# 1-Schematic_EMWAVER_V2_433_RAINSUN.net
KiCad netlist of a schematic drawn in EasyEDA
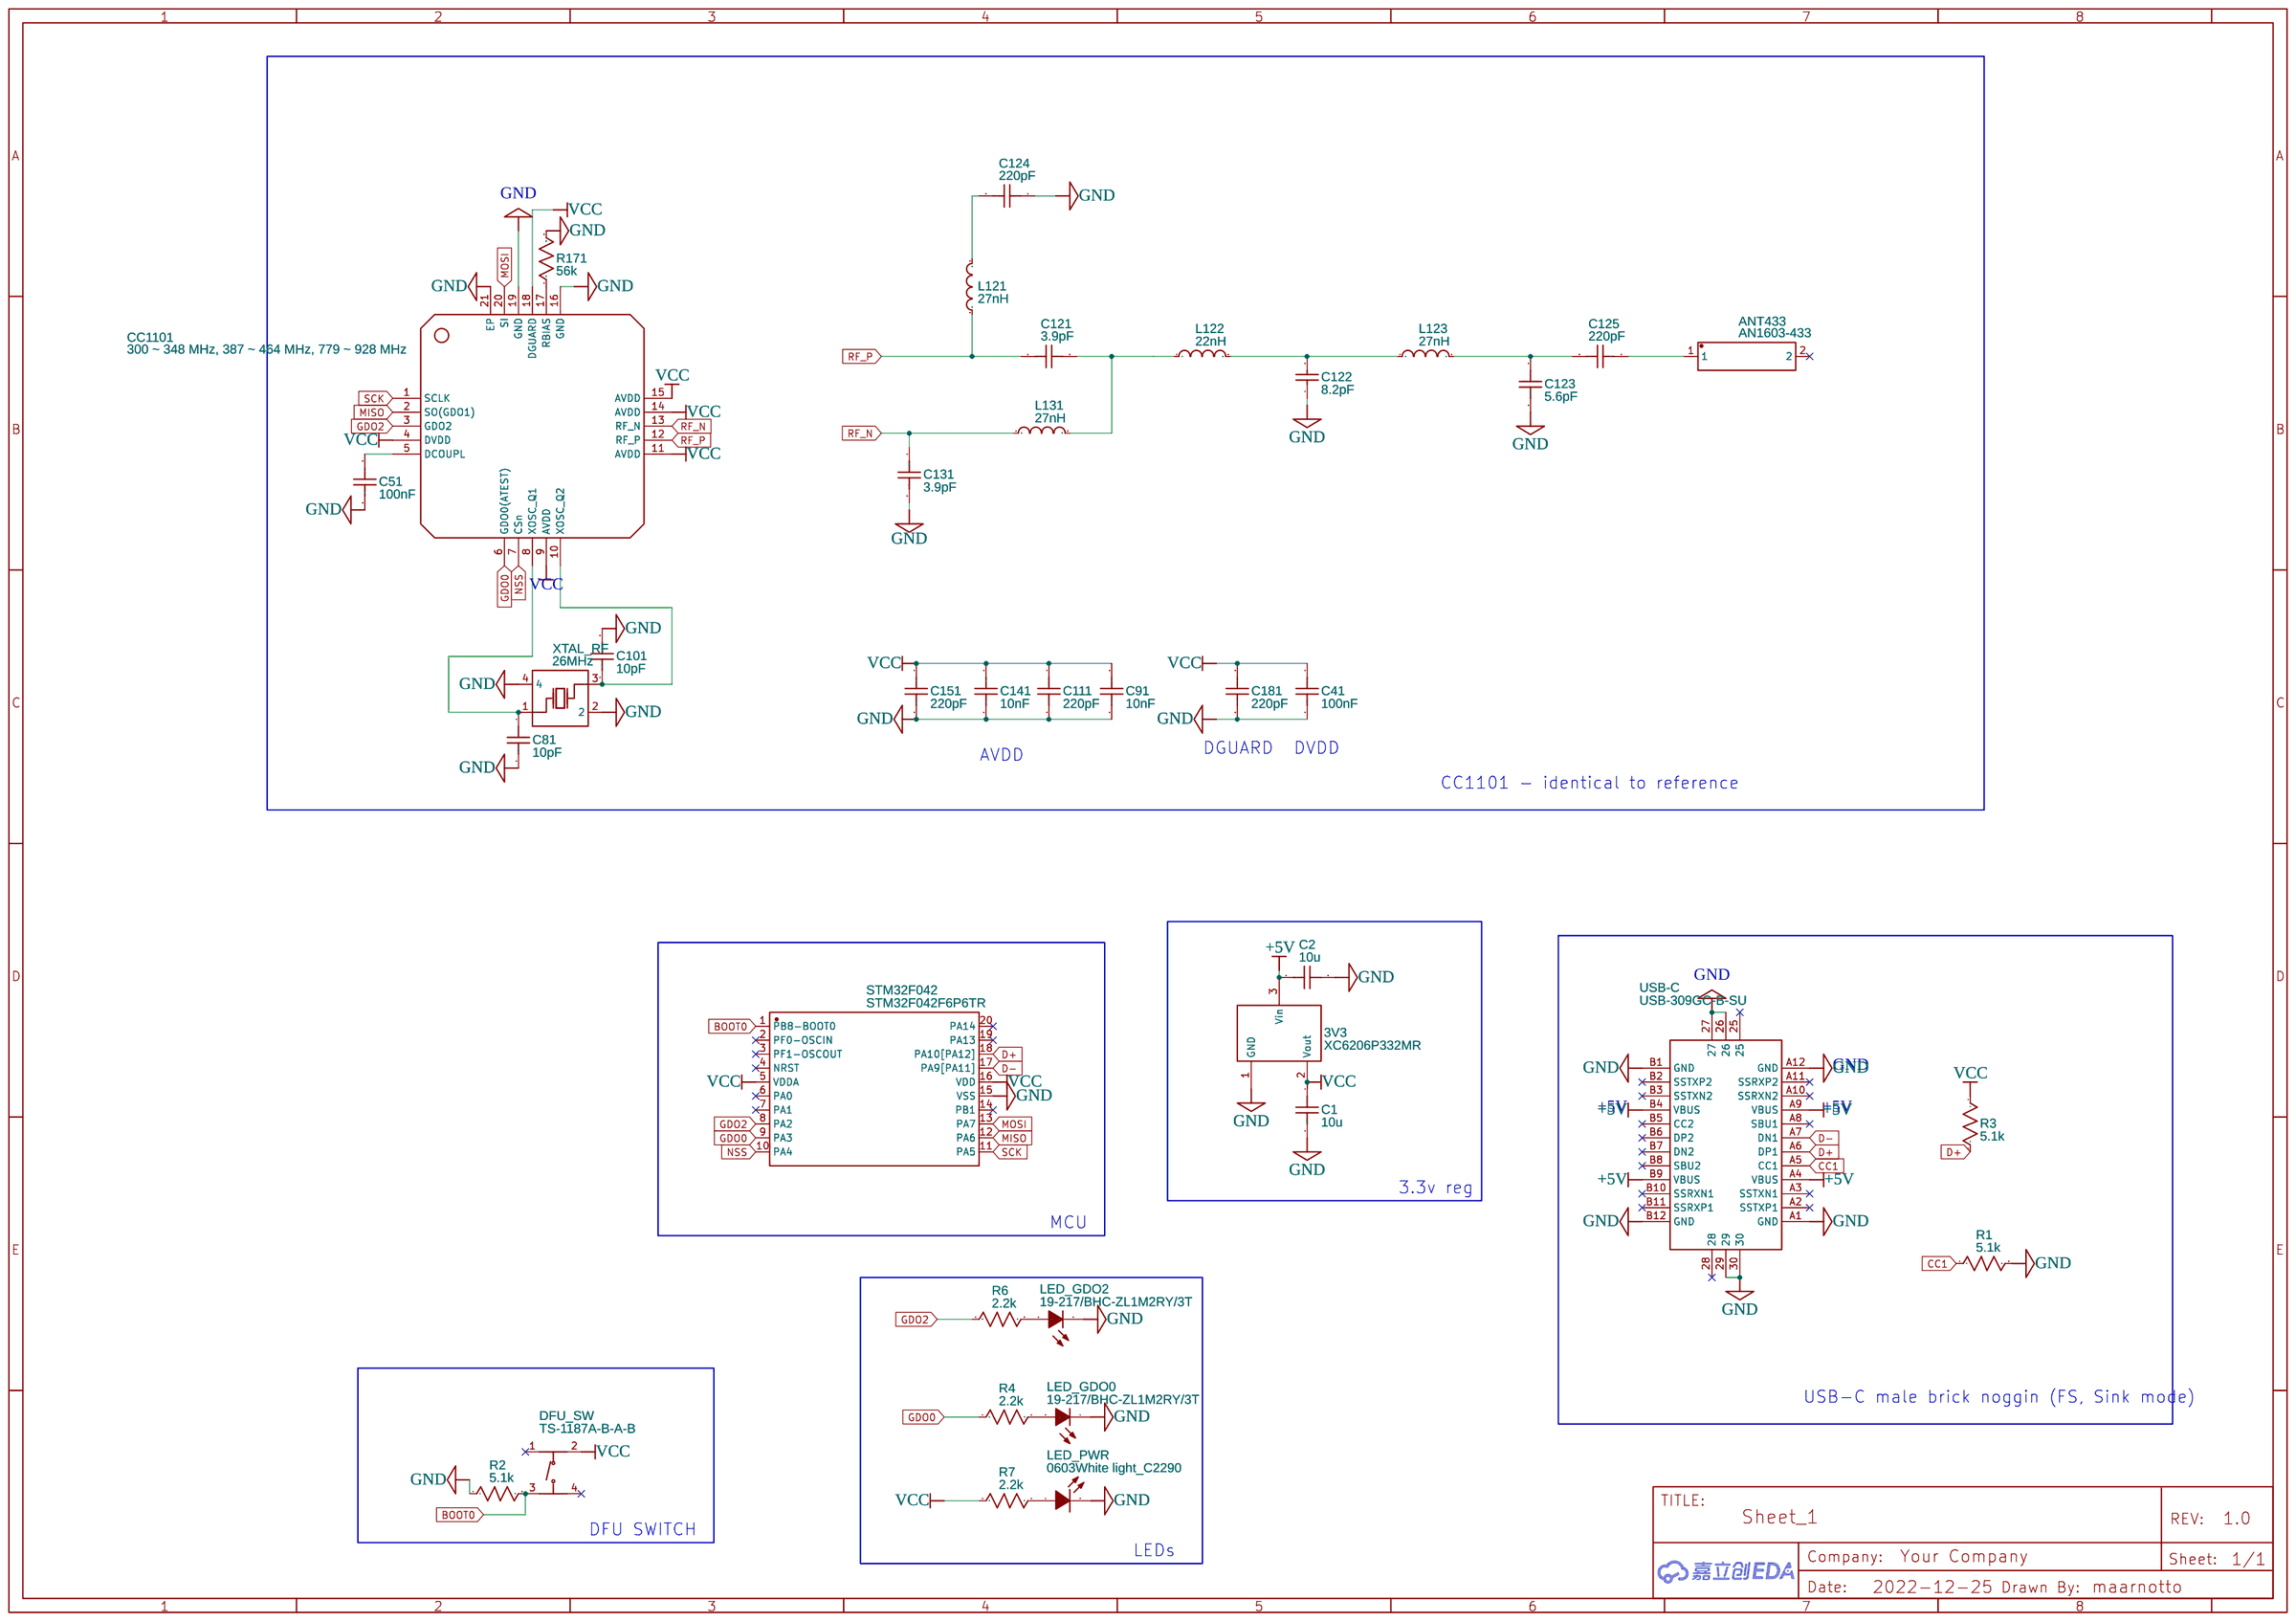
[diagram p0: schematic sheet]

(export (version "E")
  (design (tool "Eeschema 10.0.6"))
  (components
    (comp (ref "3V3")
      (value "XC6206P332MR")
      (fields (field (name "Manufacturer") "TOREX(特瑞仕)"))
      (libsource (lib "") (part "XC6206P332MR"))
    )
    (comp (ref "ANT433")
      (value "AN1603-433")
      (fields (field (name "Manufacturer") "rainsun(霖昱微)"))
      (libsource (lib "") (part "AN1603-433"))
    )
    (comp (ref "C1") (value "10u") (libsource (lib "") (part "C_0603_US")))
    (comp (ref "C2") (value "10u") (libsource (lib "") (part "C_0603_US_1")))
    (comp (ref "C41") (value "100nF") (libsource (lib "") (part "C_0402_US_1")))
    (comp (ref "C51") (value "100nF") (libsource (lib "") (part "C_0402_US_1")))
    (comp (ref "C81") (value "10pF") (libsource (lib "") (part "C_0402_US_1")))
    (comp (ref "C91") (value "10nF") (libsource (lib "") (part "C_0402_US_1")))
    (comp (ref "C101") (value "10pF") (libsource (lib "") (part "C_0402_US_2")))
    (comp (ref "C111") (value "220pF") (libsource (lib "") (part "C_0402_US_1")))
    (comp (ref "C121") (value "3.9pF") (libsource (lib "") (part "C_0402_US")))
    (comp (ref "C122")
      (value "8.2pF")
      (fields (field (name "Manufacturer Part") "0402CG8R2C500NT") (field (name "Manufacturer") "FH(风华)"))
      (libsource (lib "") (part "0402CG8R2C500NT"))
    )
    (comp (ref "C123") (value "5.6pF") (libsource (lib "") (part "C_0402_US_1")))
    (comp (ref "C124") (value "220pF") (libsource (lib "") (part "C_0402_US")))
    (comp (ref "C125") (value "220pF") (libsource (lib "") (part "C_0402_US")))
    (comp (ref "C131") (value "3.9pF") (libsource (lib "") (part "C_0402_US_1")))
    (comp (ref "C141") (value "10nF") (libsource (lib "") (part "C_0402_US_1")))
    (comp (ref "C151") (value "220pF") (libsource (lib "") (part "C_0402_US_1")))
    (comp (ref "C181") (value "220pF") (libsource (lib "") (part "C_0402_US_1")))
    (comp (ref "CC1101")
      (value "300 ~ 348 MHz, 387 ~ 464 MHz, 779 ~ 928 MHz")
      (fields (field (name "Manufacturer Part") "CC1101RGPR") (field (name "Manufacturer") "TI(德州仪器)"))
      (libsource (lib "") (part "CC1101RGPR"))
    )
    (comp (ref "DFU_SW")
      (value "TS-1187A-B-A-B")
      (fields (field (name "Manufacturer") "XKB Connectivity(中国星坤)"))
      (libsource (lib "") (part "TS-1187A-B-A-B"))
    )
    (comp (ref "L121") (value "27nH") (libsource (lib "") (part "L0402_US_1")))
    (comp (ref "L122") (value "22nH") (libsource (lib "") (part "L0402_US")))
    (comp (ref "L123") (value "27nH") (libsource (lib "") (part "L0402_US")))
    (comp (ref "L131") (value "27nH") (libsource (lib "") (part "L0402_US")))
    (comp (ref "LED_GDO0")
      (value "19-217/BHC-ZL1M2RY/3T")
      (fields (field (name "Manufacturer") "EVERLIGHT(亿光)"))
      (libsource (lib "") (part "19-217/BHC-ZL1M2RY/3T"))
    )
    (comp (ref "LED_GDO2")
      (value "19-217/BHC-ZL1M2RY/3T")
      (fields (field (name "Manufacturer") "EVERLIGHT(亿光)"))
      (libsource (lib "") (part "19-217/BHC-ZL1M2RY/3T"))
    )
    (comp (ref "LED_PWR")
      (value "0603White light_C2290")
      (fields (field (name "Manufacturer Part") "KT-0603白灯"))
      (libsource (lib "") (part "0603White light_C2290"))
    )
    (comp (ref "R1") (value "5.1k") (libsource (lib "") (part "R_0603_US")))
    (comp (ref "R2") (value "5.1k") (libsource (lib "") (part "R_0603_US")))
    (comp (ref "R3") (value "5.1k") (libsource (lib "") (part "R_0603_US_1")))
    (comp (ref "R4") (value "2.2k") (libsource (lib "") (part "R_0603_US")))
    (comp (ref "R6") (value "2.2k") (libsource (lib "") (part "R_0603_US")))
    (comp (ref "R7") (value "2.2k") (libsource (lib "") (part "R_0603_US")))
    (comp (ref "R171") (value "56k") (libsource (lib "") (part "R_0402_US")))
    (comp (ref "STM32F042")
      (value "STM32F042F6P6TR")
      (fields (field (name "Manufacturer") "ST(意法半导体)"))
      (libsource (lib "") (part "STM32F042F6P6TR"))
    )
    (comp (ref "USB-C")
      (value "USB-309GC-B-SU")
      (fields (field (name "Manufacturer") "HOOYA"))
      (libsource (lib "") (part "USB-309GC-B-SU"))
    )
    (comp (ref "XTAL_RF")
      (value "26MHz")
      (fields (field (name "Manufacturer Part") "3S26000333") (field (name "Manufacturer") "YL(惠伦晶体)"))
      (libsource (lib "") (part "3S26000333"))
    )
  )
  (nets
    (net (code "1") (name "+5V") (class "Default")
      (node (ref "3V3") (pin "3") (pinfunction "Vin_3") (pintype "unspecified"))
      (node (ref "C2") (pin "2") (pinfunction "2_2") (pintype "unspecified"))
      (node (ref "USB-C") (pin "A4") (pinfunction "VBUS_A4") (pintype "unspecified"))
      (node (ref "USB-C") (pin "A9") (pinfunction "VBUS_A9") (pintype "unspecified"))
      (node (ref "USB-C") (pin "B4") (pinfunction "VBUS_B4") (pintype "unspecified"))
      (node (ref "USB-C") (pin "B9") (pinfunction "VBUS_B9") (pintype "unspecified"))
    )
    (net (code "2") (name "BOOT0") (class "Default")
      (node (ref "DFU_SW") (pin "3") (pinfunction "C_3") (pintype "unspecified"))
      (node (ref "R2") (pin "2") (pinfunction "2_2") (pintype "unspecified"))
      (node (ref "STM32F042") (pin "1") (pinfunction "PB8-BOOT0_1") (pintype "unspecified"))
    )
    (net (code "3") (name "CC1") (class "Default")
      (node (ref "R1") (pin "1") (pinfunction "1_1") (pintype "unspecified"))
      (node (ref "USB-C") (pin "A5") (pinfunction "CC1_A5") (pintype "unspecified"))
    )
    (net (code "4") (name "D+") (class "Default")
      (node (ref "R3") (pin "2") (pinfunction "2_2") (pintype "unspecified"))
      (node (ref "STM32F042") (pin "18") (pinfunction "PA10[PA12]_18") (pintype "unspecified"))
      (node (ref "USB-C") (pin "A6") (pinfunction "DP1_A6") (pintype "unspecified"))
    )
    (net (code "5") (name "D-") (class "Default")
      (node (ref "STM32F042") (pin "17") (pinfunction "PA9[PA11]_17") (pintype "unspecified"))
      (node (ref "USB-C") (pin "A7") (pinfunction "DN1_A7") (pintype "unspecified"))
    )
    (net (code "6") (name "GDO0") (class "Default")
      (node (ref "CC1101") (pin "6") (pinfunction "GDO0(ATEST)_6") (pintype "unspecified"))
      (node (ref "R4") (pin "1") (pinfunction "1_1") (pintype "unspecified"))
      (node (ref "STM32F042") (pin "9") (pinfunction "PA3_9") (pintype "unspecified"))
    )
    (net (code "7") (name "GDO2") (class "Default")
      (node (ref "CC1101") (pin "3") (pinfunction "GDO2_3") (pintype "unspecified"))
      (node (ref "R6") (pin "1") (pinfunction "1_1") (pintype "unspecified"))
      (node (ref "STM32F042") (pin "8") (pinfunction "PA2_8") (pintype "unspecified"))
    )
    (net (code "8") (name "GND") (class "Default")
      (node (ref "3V3") (pin "1") (pinfunction "GND_1") (pintype "unspecified"))
      (node (ref "C1") (pin "2") (pinfunction "2_2") (pintype "unspecified"))
      (node (ref "C101") (pin "2") (pinfunction "2_2") (pintype "unspecified"))
      (node (ref "C111") (pin "2") (pinfunction "2_2") (pintype "unspecified"))
      (node (ref "C122") (pin "1") (pinfunction "1_1") (pintype "input"))
      (node (ref "C123") (pin "2") (pinfunction "2_2") (pintype "unspecified"))
      (node (ref "C124") (pin "1") (pinfunction "1_1") (pintype "unspecified"))
      (node (ref "C131") (pin "2") (pinfunction "2_2") (pintype "unspecified"))
      (node (ref "C141") (pin "2") (pinfunction "2_2") (pintype "unspecified"))
      (node (ref "C151") (pin "2") (pinfunction "2_2") (pintype "unspecified"))
      (node (ref "C181") (pin "2") (pinfunction "2_2") (pintype "unspecified"))
      (node (ref "C2") (pin "1") (pinfunction "1_1") (pintype "unspecified"))
      (node (ref "C41") (pin "2") (pinfunction "2_2") (pintype "unspecified"))
      (node (ref "C51") (pin "2") (pinfunction "2_2") (pintype "unspecified"))
      (node (ref "C81") (pin "2") (pinfunction "2_2") (pintype "unspecified"))
      (node (ref "C91") (pin "2") (pinfunction "2_2") (pintype "unspecified"))
      (node (ref "CC1101") (pin "16") (pinfunction "GND_16") (pintype "unspecified"))
      (node (ref "CC1101") (pin "19") (pinfunction "GND_19") (pintype "unspecified"))
      (node (ref "CC1101") (pin "21") (pinfunction "EP_21") (pintype "unspecified"))
      (node (ref "LED_GDO0") (pin "1") (pinfunction "C_1") (pintype "input"))
      (node (ref "LED_GDO2") (pin "1") (pinfunction "C_1") (pintype "input"))
      (node (ref "LED_PWR") (pin "2") (pinfunction "K_2") (pintype "unspecified"))
      (node (ref "R1") (pin "2") (pinfunction "2_2") (pintype "unspecified"))
      (node (ref "R171") (pin "2") (pinfunction "2_2") (pintype "unspecified"))
      (node (ref "R2") (pin "1") (pinfunction "1_1") (pintype "unspecified"))
      (node (ref "STM32F042") (pin "15") (pinfunction "VSS_15") (pintype "unspecified"))
      (node (ref "USB-C") (pin "26") (pinfunction "26_26") (pintype "unspecified"))
      (node (ref "USB-C") (pin "27") (pinfunction "27_27") (pintype "unspecified"))
      (node (ref "USB-C") (pin "29") (pinfunction "29_29") (pintype "unspecified"))
      (node (ref "USB-C") (pin "30") (pinfunction "30_30") (pintype "unspecified"))
      (node (ref "USB-C") (pin "A1") (pinfunction "GND_A1") (pintype "unspecified"))
      (node (ref "USB-C") (pin "A12") (pinfunction "GND_A12") (pintype "unspecified"))
      (node (ref "USB-C") (pin "B1") (pinfunction "GND_B1") (pintype "unspecified"))
      (node (ref "USB-C") (pin "B12") (pinfunction "GND_B12") (pintype "unspecified"))
      (node (ref "XTAL_RF") (pin "2") (pinfunction "2_2") (pintype "unspecified"))
      (node (ref "XTAL_RF") (pin "4") (pinfunction "4_4") (pintype "unspecified"))
    )
    (net (code "9") (name "MISO") (class "Default")
      (node (ref "CC1101") (pin "2") (pinfunction "SO(GDO1)_2") (pintype "unspecified"))
      (node (ref "STM32F042") (pin "12") (pinfunction "PA6_12") (pintype "unspecified"))
    )
    (net (code "10") (name "MOSI") (class "Default")
      (node (ref "CC1101") (pin "20") (pinfunction "SI_20") (pintype "unspecified"))
      (node (ref "STM32F042") (pin "13") (pinfunction "PA7_13") (pintype "unspecified"))
    )
    (net (code "11") (name "NSS") (class "Default")
      (node (ref "CC1101") (pin "7") (pinfunction "CSn_7") (pintype "unspecified"))
      (node (ref "STM32F042") (pin "10") (pinfunction "PA4_10") (pintype "unspecified"))
    )
    (net (code "12") (name "Net-(ANT433-Pad1)") (class "Default")
      (node (ref "ANT433") (pin "1") (pinfunction "1_1") (pintype "unspecified"))
      (node (ref "C125") (pin "1") (pinfunction "1_1") (pintype "unspecified"))
    )
    (net (code "13") (name "Net-(C121-Pad1)") (class "Default")
      (node (ref "C121") (pin "1") (pinfunction "1_1") (pintype "unspecified"))
      (node (ref "L122") (pin "1") (pinfunction "1_1") (pintype "unspecified"))
      (node (ref "L131") (pin "2") (pinfunction "2_2") (pintype "unspecified"))
    )
    (net (code "14") (name "Net-(C122-Pad2)") (class "Default")
      (node (ref "C122") (pin "2") (pinfunction "2_2") (pintype "input"))
      (node (ref "L122") (pin "2") (pinfunction "2_2") (pintype "unspecified"))
      (node (ref "L123") (pin "1") (pinfunction "1_1") (pintype "unspecified"))
    )
    (net (code "15") (name "Net-(C123-Pad1)") (class "Default")
      (node (ref "C123") (pin "1") (pinfunction "1_1") (pintype "unspecified"))
      (node (ref "C125") (pin "2") (pinfunction "2_2") (pintype "unspecified"))
      (node (ref "L123") (pin "2") (pinfunction "2_2") (pintype "unspecified"))
    )
    (net (code "16") (name "Net-(C124-Pad2)") (class "Default")
      (node (ref "C124") (pin "2") (pinfunction "2_2") (pintype "unspecified"))
      (node (ref "L121") (pin "2") (pinfunction "2_2") (pintype "unspecified"))
    )
    (net (code "17") (name "Net-(CC1101-DCOUPL)") (class "Default")
      (node (ref "C51") (pin "1") (pinfunction "1_1") (pintype "unspecified"))
      (node (ref "CC1101") (pin "5") (pinfunction "DCOUPL_5") (pintype "unspecified"))
    )
    (net (code "18") (name "Net-(CC1101-RBIAS)") (class "Default")
      (node (ref "CC1101") (pin "17") (pinfunction "RBIAS_17") (pintype "unspecified"))
      (node (ref "R171") (pin "1") (pinfunction "1_1") (pintype "unspecified"))
    )
    (net (code "19") (name "Net-(CC1101-XOSC_Q1)") (class "Default")
      (node (ref "C81") (pin "1") (pinfunction "1_1") (pintype "unspecified"))
      (node (ref "CC1101") (pin "8") (pinfunction "XOSC_Q1_8") (pintype "unspecified"))
      (node (ref "XTAL_RF") (pin "1") (pinfunction "OSC1_1") (pintype "unspecified"))
    )
    (net (code "20") (name "Net-(CC1101-XOSC_Q2)") (class "Default")
      (node (ref "C101") (pin "1") (pinfunction "1_1") (pintype "unspecified"))
      (node (ref "CC1101") (pin "10") (pinfunction "XOSC_Q2_10") (pintype "unspecified"))
      (node (ref "XTAL_RF") (pin "3") (pinfunction "OSC2_3") (pintype "unspecified"))
    )
    (net (code "21") (name "Net-(LED_GDO0-A)") (class "Default")
      (node (ref "LED_GDO0") (pin "2") (pinfunction "A_2") (pintype "input"))
      (node (ref "R4") (pin "2") (pinfunction "2_2") (pintype "unspecified"))
    )
    (net (code "22") (name "Net-(LED_GDO2-A)") (class "Default")
      (node (ref "LED_GDO2") (pin "2") (pinfunction "A_2") (pintype "input"))
      (node (ref "R6") (pin "2") (pinfunction "2_2") (pintype "unspecified"))
    )
    (net (code "23") (name "Net-(LED_PWR-A)") (class "Default")
      (node (ref "LED_PWR") (pin "1") (pinfunction "A_1") (pintype "unspecified"))
      (node (ref "R7") (pin "2") (pinfunction "2_2") (pintype "unspecified"))
    )
    (net (code "24") (name "RF_N") (class "Default")
      (node (ref "C131") (pin "1") (pinfunction "1_1") (pintype "unspecified"))
      (node (ref "CC1101") (pin "13") (pinfunction "RF_N_13") (pintype "unspecified"))
      (node (ref "L131") (pin "1") (pinfunction "1_1") (pintype "unspecified"))
    )
    (net (code "25") (name "RF_P") (class "Default")
      (node (ref "C121") (pin "2") (pinfunction "2_2") (pintype "unspecified"))
      (node (ref "CC1101") (pin "12") (pinfunction "RF_P_12") (pintype "unspecified"))
      (node (ref "L121") (pin "1") (pinfunction "1_1") (pintype "unspecified"))
    )
    (net (code "26") (name "SCK") (class "Default")
      (node (ref "CC1101") (pin "1") (pinfunction "SCLK_1") (pintype "unspecified"))
      (node (ref "STM32F042") (pin "11") (pinfunction "PA5_11") (pintype "unspecified"))
    )
    (net (code "27") (name "VCC") (class "Default")
      (node (ref "3V3") (pin "2") (pinfunction "Vout_2") (pintype "unspecified"))
      (node (ref "C1") (pin "1") (pinfunction "1_1") (pintype "unspecified"))
      (node (ref "C111") (pin "1") (pinfunction "1_1") (pintype "unspecified"))
      (node (ref "C141") (pin "1") (pinfunction "1_1") (pintype "unspecified"))
      (node (ref "C151") (pin "1") (pinfunction "1_1") (pintype "unspecified"))
      (node (ref "C181") (pin "1") (pinfunction "1_1") (pintype "unspecified"))
      (node (ref "C41") (pin "1") (pinfunction "1_1") (pintype "unspecified"))
      (node (ref "C91") (pin "1") (pinfunction "1_1") (pintype "unspecified"))
      (node (ref "CC1101") (pin "11") (pinfunction "AVDD_11") (pintype "unspecified"))
      (node (ref "CC1101") (pin "14") (pinfunction "AVDD_14") (pintype "unspecified"))
      (node (ref "CC1101") (pin "15") (pinfunction "AVDD_15") (pintype "unspecified"))
      (node (ref "CC1101") (pin "18") (pinfunction "DGUARD_18") (pintype "unspecified"))
      (node (ref "CC1101") (pin "4") (pinfunction "DVDD_4") (pintype "unspecified"))
      (node (ref "CC1101") (pin "9") (pinfunction "AVDD_9") (pintype "unspecified"))
      (node (ref "DFU_SW") (pin "2") (pinfunction "B_2") (pintype "unspecified"))
      (node (ref "R3") (pin "1") (pinfunction "1_1") (pintype "unspecified"))
      (node (ref "R7") (pin "1") (pinfunction "1_1") (pintype "unspecified"))
      (node (ref "STM32F042") (pin "16") (pinfunction "VDD_16") (pintype "unspecified"))
      (node (ref "STM32F042") (pin "5") (pinfunction "VDDA_5") (pintype "unspecified"))
    )
    (net (code "28") (name "unconnected-(ANT433-Pad2)") (class "Default")
      (node (ref "ANT433") (pin "2") (pinfunction "2_2") (pintype "unspecified+no_connect"))
    )
    (net (code "29") (name "unconnected-(DFU_SW-A-Pad1)") (class "Default")
      (node (ref "DFU_SW") (pin "1") (pinfunction "A_1") (pintype "unspecified+no_connect"))
    )
    (net (code "30") (name "unconnected-(DFU_SW-D-Pad4)") (class "Default")
      (node (ref "DFU_SW") (pin "4") (pinfunction "D_4") (pintype "unspecified+no_connect"))
    )
    (net (code "31") (name "unconnected-(STM32F042-NRST-Pad4)") (class "Default")
      (node (ref "STM32F042") (pin "4") (pinfunction "NRST_4") (pintype "unspecified+no_connect"))
    )
    (net (code "32") (name "unconnected-(STM32F042-PA0-Pad6)") (class "Default")
      (node (ref "STM32F042") (pin "6") (pinfunction "PA0_6") (pintype "unspecified+no_connect"))
    )
    (net (code "33") (name "unconnected-(STM32F042-PA1-Pad7)") (class "Default")
      (node (ref "STM32F042") (pin "7") (pinfunction "PA1_7") (pintype "unspecified+no_connect"))
    )
    (net (code "34") (name "unconnected-(STM32F042-PA13-Pad19)") (class "Default")
      (node (ref "STM32F042") (pin "19") (pinfunction "PA13_19") (pintype "unspecified+no_connect"))
    )
    (net (code "35") (name "unconnected-(STM32F042-PA14-Pad20)") (class "Default")
      (node (ref "STM32F042") (pin "20") (pinfunction "PA14_20") (pintype "unspecified+no_connect"))
    )
    (net (code "36") (name "unconnected-(STM32F042-PB1-Pad14)") (class "Default")
      (node (ref "STM32F042") (pin "14") (pinfunction "PB1_14") (pintype "unspecified+no_connect"))
    )
    (net (code "37") (name "unconnected-(STM32F042-PF0-OSCIN-Pad2)") (class "Default")
      (node (ref "STM32F042") (pin "2") (pinfunction "PF0-OSCIN_2") (pintype "unspecified+no_connect"))
    )
    (net (code "38") (name "unconnected-(STM32F042-PF1-OSCOUT-Pad3)") (class "Default")
      (node (ref "STM32F042") (pin "3") (pinfunction "PF1-OSCOUT_3") (pintype "unspecified+no_connect"))
    )
    (net (code "39") (name "unconnected-(USB-C-CC2-PadB5)") (class "Default")
      (node (ref "USB-C") (pin "B5") (pinfunction "CC2_B5") (pintype "unspecified+no_connect"))
    )
    (net (code "40") (name "unconnected-(USB-C-DN2-PadB7)") (class "Default")
      (node (ref "USB-C") (pin "B7") (pinfunction "DN2_B7") (pintype "unspecified+no_connect"))
    )
    (net (code "41") (name "unconnected-(USB-C-DP2-PadB6)") (class "Default")
      (node (ref "USB-C") (pin "B6") (pinfunction "DP2_B6") (pintype "unspecified+no_connect"))
    )
    (net (code "42") (name "unconnected-(USB-C-Pad25)") (class "Default")
      (node (ref "USB-C") (pin "25") (pinfunction "25_25") (pintype "unspecified+no_connect"))
    )
    (net (code "43") (name "unconnected-(USB-C-Pad28)") (class "Default")
      (node (ref "USB-C") (pin "28") (pinfunction "28_28") (pintype "unspecified+no_connect"))
    )
    (net (code "44") (name "unconnected-(USB-C-SBU1-PadA8)") (class "Default")
      (node (ref "USB-C") (pin "A8") (pinfunction "SBU1_A8") (pintype "unspecified+no_connect"))
    )
    (net (code "45") (name "unconnected-(USB-C-SBU2-PadB8)") (class "Default")
      (node (ref "USB-C") (pin "B8") (pinfunction "SBU2_B8") (pintype "unspecified+no_connect"))
    )
    (net (code "46") (name "unconnected-(USB-C-SSRXN1-PadB10)") (class "Default")
      (node (ref "USB-C") (pin "B10") (pinfunction "SSRXN1_B10") (pintype "unspecified+no_connect"))
    )
    (net (code "47") (name "unconnected-(USB-C-SSRXN2-PadA10)") (class "Default")
      (node (ref "USB-C") (pin "A10") (pinfunction "SSRXN2_A10") (pintype "unspecified+no_connect"))
    )
    (net (code "48") (name "unconnected-(USB-C-SSRXP1-PadB11)") (class "Default")
      (node (ref "USB-C") (pin "B11") (pinfunction "SSRXP1_B11") (pintype "unspecified+no_connect"))
    )
    (net (code "49") (name "unconnected-(USB-C-SSRXP2-PadA11)") (class "Default")
      (node (ref "USB-C") (pin "A11") (pinfunction "SSRXP2_A11") (pintype "unspecified+no_connect"))
    )
    (net (code "50") (name "unconnected-(USB-C-SSTXN1-PadA3)") (class "Default")
      (node (ref "USB-C") (pin "A3") (pinfunction "SSTXN1_A3") (pintype "unspecified+no_connect"))
    )
    (net (code "51") (name "unconnected-(USB-C-SSTXN2-PadB3)") (class "Default")
      (node (ref "USB-C") (pin "B3") (pinfunction "SSTXN2_B3") (pintype "unspecified+no_connect"))
    )
    (net (code "52") (name "unconnected-(USB-C-SSTXP1-PadA2)") (class "Default")
      (node (ref "USB-C") (pin "A2") (pinfunction "SSTXP1_A2") (pintype "unspecified+no_connect"))
    )
    (net (code "53") (name "unconnected-(USB-C-SSTXP2-PadB2)") (class "Default")
      (node (ref "USB-C") (pin "B2") (pinfunction "SSTXP2_B2") (pintype "unspecified+no_connect"))
    )
  )
)
